# Kiwi_Rev_3_1S.net
KiCad netlist of a schematic drawn in EAGLE
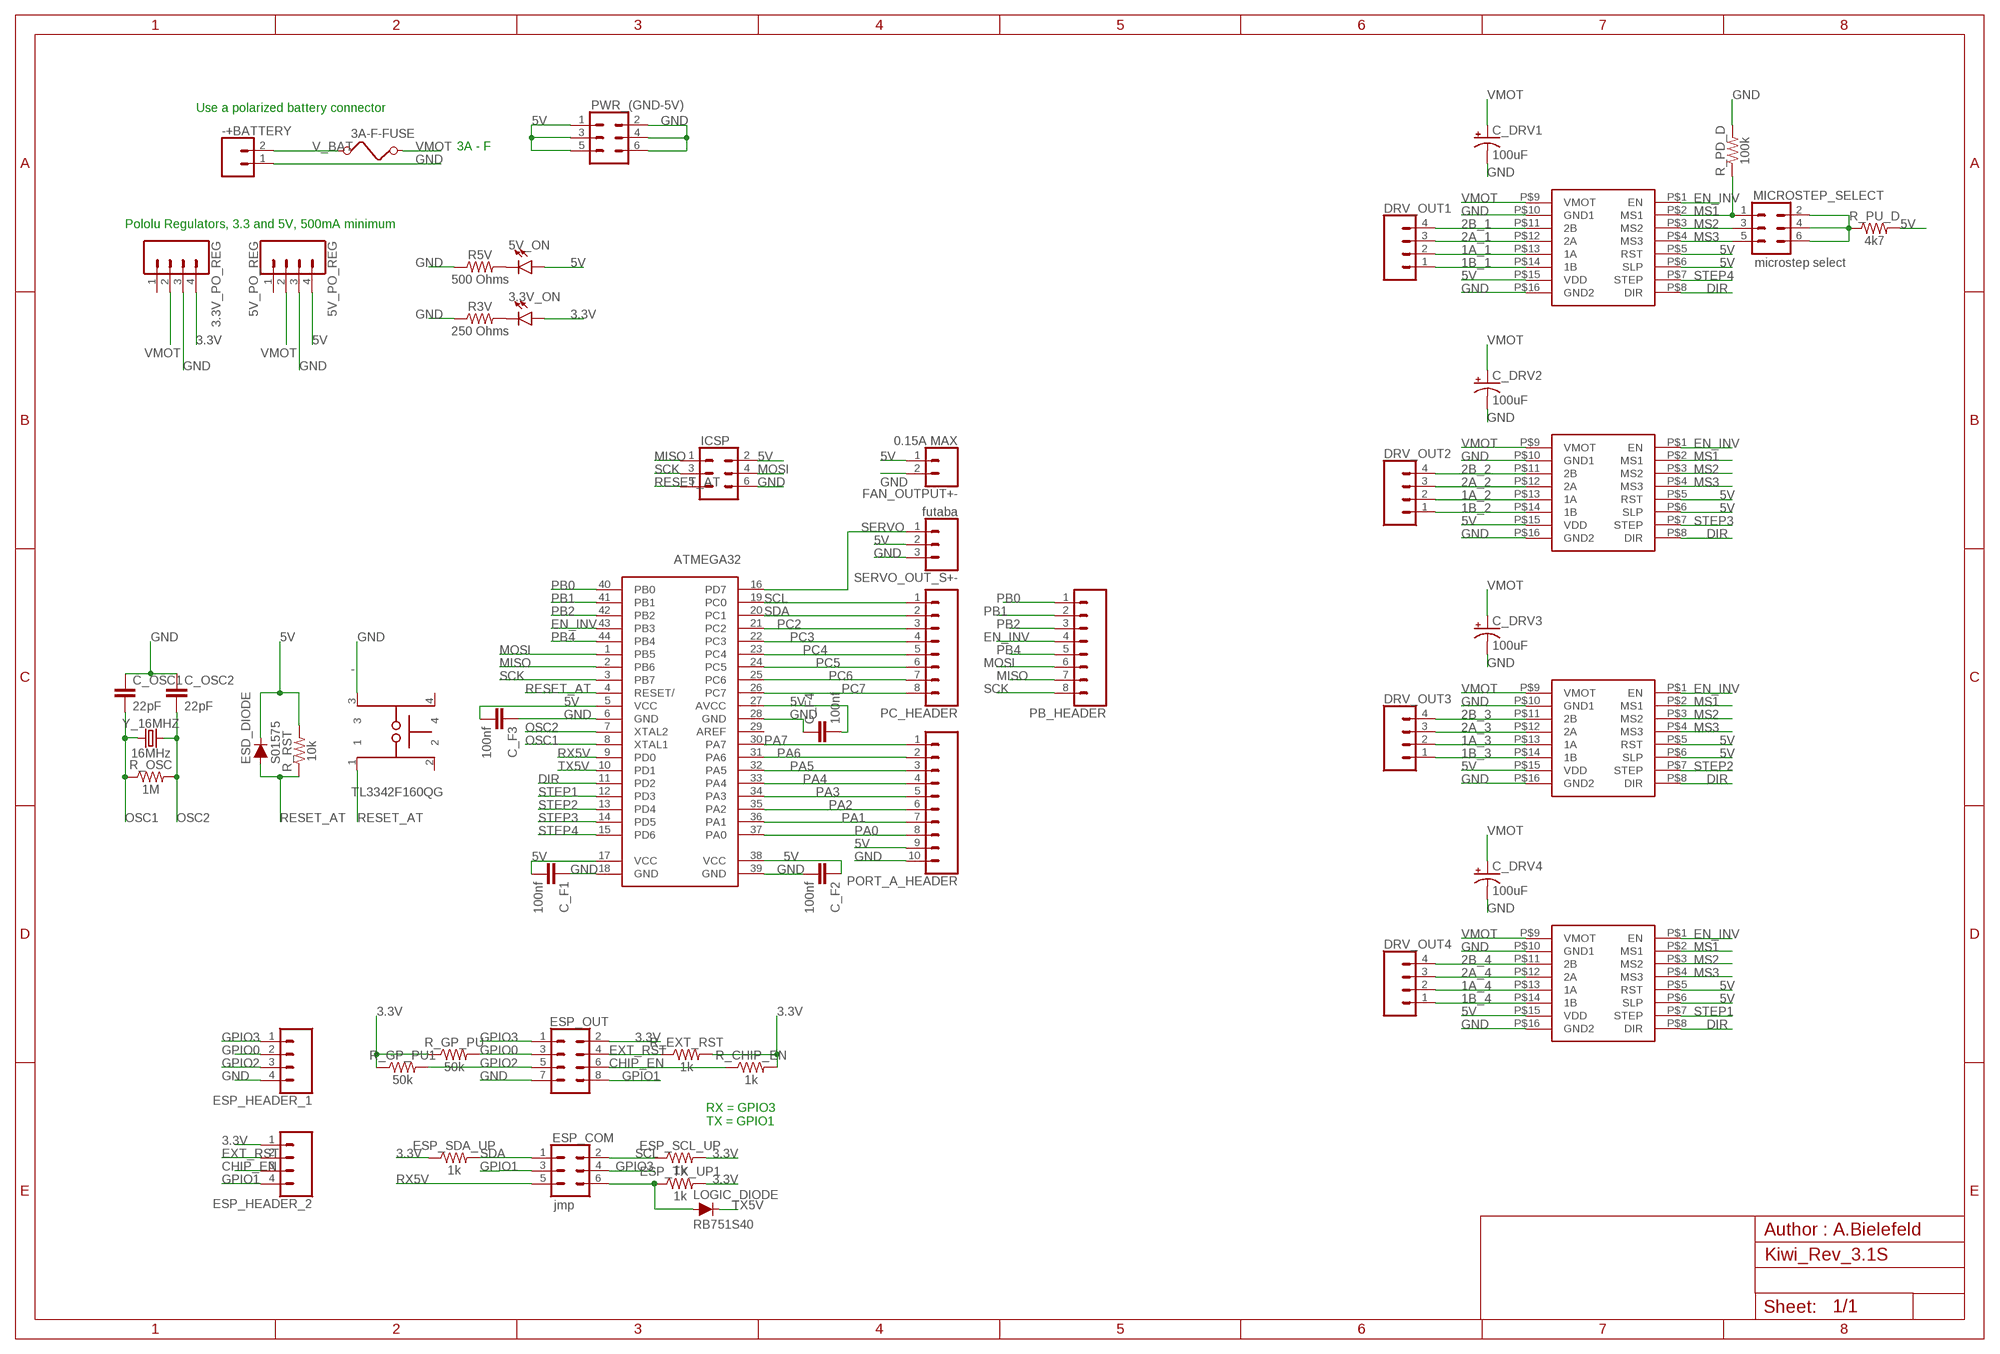
[diagram p0: schematic, sheet 1]

(export (version "E")
  (design (tool "Eeschema 10.0.6"))
  (components
    (comp (ref "-")
      (value "TL3342F160QG")
      (footprint "eagle-import:SW_TL3342F160QG")
      (fields (field (name "MF") "E-Switch"))
      (libsource (lib "eagle-import") (part "TL3342F160QG"))
    )
    (comp (ref "-+BATTERY")
      (value "CONN_023.5MM")
      (footprint "eagle-import:SCREWTERMINAL-3.5MM-2")
      (libsource (lib "eagle-import") (part "CONN_023.5MM"))
    )
    (comp (ref "3.3V_ON")
      (value "LED1206")
      (footprint "eagle-import:LED-1206")
      (libsource (lib "eagle-import") (part "LED1206"))
    )
    (comp (ref "3.3V_PO_REG")
      (value "CONN_04")
      (footprint "eagle-import:1X04")
      (libsource (lib "eagle-import") (part "CONN_04"))
    )
    (comp (ref "3A-F-FUSE")
      (value "FUSE")
      (footprint "eagle-import:FUSE")
      (libsource (lib "eagle-import") (part "FUSE"))
    )
    (comp (ref "5V_ON")
      (value "LED1206")
      (footprint "eagle-import:LED-1206")
      (libsource (lib "eagle-import") (part "LED1206"))
    )
    (comp (ref "5V_PO_REG")
      (value "5V_PO_REG")
      (footprint "eagle-import:1X04")
      (libsource (lib "eagle-import") (part "CONN_04"))
    )
    (comp (ref "ATMEGA32")
      (value "ATMEGA32")
      (footprint "eagle-import:QFP80P1200X1200X120-44N")
      (libsource (lib "eagle-import") (part "ATMEGA32"))
    )
    (comp (ref "C_DRV1")
      (value "100uF")
      (footprint "eagle-import:CPOL-RADIAL-2.5MM-6.5MM")
      (libsource (lib "eagle-import") (part "100UF-POLAR-RADIAL-2.5MM-25V-20%"))
    )
    (comp (ref "C_DRV2")
      (value "100uF")
      (footprint "eagle-import:CPOL-RADIAL-2.5MM-6.5MM")
      (libsource (lib "eagle-import") (part "100UF-POLAR-RADIAL-2.5MM-25V-20%"))
    )
    (comp (ref "C_DRV3")
      (value "100uF")
      (footprint "eagle-import:CPOL-RADIAL-2.5MM-6.5MM")
      (libsource (lib "eagle-import") (part "100UF-POLAR-RADIAL-2.5MM-25V-20%"))
    )
    (comp (ref "C_DRV4")
      (value "100uF")
      (footprint "eagle-import:CPOL-RADIAL-2.5MM-6.5MM")
      (libsource (lib "eagle-import") (part "100UF-POLAR-RADIAL-2.5MM-25V-20%"))
    )
    (comp (ref "C_F1")
      (value "100nf")
      (footprint "eagle-import:0603")
      (libsource (lib "eagle-import") (part "2.2UF-0603-10V-20%"))
    )
    (comp (ref "C_F2")
      (value "100nf")
      (footprint "eagle-import:0603")
      (libsource (lib "eagle-import") (part "2.2UF-0603-10V-20%"))
    )
    (comp (ref "C_F3")
      (value "100nf")
      (footprint "eagle-import:0603")
      (libsource (lib "eagle-import") (part "2.2UF-0603-10V-20%"))
    )
    (comp (ref "C_F4")
      (value "100nf")
      (footprint "eagle-import:0603")
      (libsource (lib "eagle-import") (part "2.2UF-0603-10V-20%"))
    )
    (comp (ref "C_OSC1")
      (value "22pF")
      (footprint "eagle-import:1206")
      (libsource (lib "eagle-import") (part "2.2UF-1206-50V-10%"))
    )
    (comp (ref "C_OSC2")
      (value "22pF")
      (footprint "eagle-import:1206")
      (libsource (lib "eagle-import") (part "2.2UF-1206-50V-10%"))
    )
    (comp (ref "DRIVER1")
      (value "POLOLU_A4988")
      (footprint "eagle-import:POLOLU_CARRIER")
      (libsource (lib "eagle-import") (part "POLOLU_A4988"))
    )
    (comp (ref "DRIVER2")
      (value "POLOLU_A4988")
      (footprint "eagle-import:POLOLU_CARRIER")
      (libsource (lib "eagle-import") (part "POLOLU_A4988"))
    )
    (comp (ref "DRIVER3")
      (value "POLOLU_A4988")
      (footprint "eagle-import:POLOLU_CARRIER")
      (libsource (lib "eagle-import") (part "POLOLU_A4988"))
    )
    (comp (ref "DRIVER4")
      (value "POLOLU_A4988")
      (footprint "eagle-import:POLOLU_CARRIER")
      (libsource (lib "eagle-import") (part "POLOLU_A4988"))
    )
    (comp (ref "DRV_OUT1")
      (value "CONN_04")
      (footprint "eagle-import:1X04")
      (libsource (lib "eagle-import") (part "CONN_04"))
    )
    (comp (ref "DRV_OUT2")
      (value "CONN_04")
      (footprint "eagle-import:1X04")
      (libsource (lib "eagle-import") (part "CONN_04"))
    )
    (comp (ref "DRV_OUT3")
      (value "CONN_04")
      (footprint "eagle-import:1X04")
      (libsource (lib "eagle-import") (part "CONN_04"))
    )
    (comp (ref "DRV_OUT4")
      (value "CONN_04")
      (footprint "eagle-import:1X04")
      (libsource (lib "eagle-import") (part "CONN_04"))
    )
    (comp (ref "ESD_DIODE")
      (value "S01575")
      (footprint "eagle-import:1206")
      (libsource (lib "eagle-import") (part "S01575"))
    )
    (comp (ref "ESP_COM")
      (value "jmp")
      (footprint "eagle-import:2X3")
      (libsource (lib "eagle-import") (part "CONN_03X2FEMALE"))
    )
    (comp (ref "ESP_HEADER_1")
      (value "CONN_04")
      (footprint "eagle-import:1X04")
      (libsource (lib "eagle-import") (part "CONN_04"))
    )
    (comp (ref "ESP_HEADER_2")
      (value "CONN_04")
      (footprint "eagle-import:1X04")
      (libsource (lib "eagle-import") (part "CONN_04"))
    )
    (comp (ref "ESP_OUT")
      (value "CONN_04X2")
      (footprint "eagle-import:2X4")
      (libsource (lib "eagle-import") (part "CONN_04X2"))
    )
    (comp (ref "ESP_SCL_UP")
      (value "1k")
      (footprint "eagle-import:1206")
      (libsource (lib "eagle-import") (part "10OHM-1206-1/4W-1%"))
    )
    (comp (ref "ESP_SDA_UP")
      (value "1k")
      (footprint "eagle-import:1206")
      (libsource (lib "eagle-import") (part "10OHM-1206-1/4W-1%"))
    )
    (comp (ref "ESP_TX_UP1")
      (value "1k")
      (footprint "eagle-import:1206")
      (libsource (lib "eagle-import") (part "10OHM-1206-1/4W-1%"))
    )
    (comp (ref "FAN_OUTPUT+-")
      (value "0.15A MAX")
      (footprint "eagle-import:1X02")
      (libsource (lib "eagle-import") (part "CONN_02"))
    )
    (comp (ref "ICSP")
      (value "CONN_03X22X3_SILK_MALE_PTH")
      (footprint "eagle-import:2X3")
      (libsource (lib "eagle-import") (part "CONN_03X22X3_SILK_MALE_PTH"))
    )
    (comp (ref "LOGIC_DIODE")
      (value "RB751S40")
      (footprint "eagle-import:SOD523")
      (libsource (lib "eagle-import") (part "RB751S40"))
    )
    (comp (ref "MICROSTEP_SELECT")
      (value "microstep select")
      (footprint "eagle-import:2X3")
      (libsource (lib "eagle-import") (part "CONN_03X2FEMALE"))
    )
    (comp (ref "PB_HEADER")
      (value "CONN_08\"")
      (footprint "eagle-import:1X08")
      (libsource (lib "eagle-import") (part "CONN_08{dblquote}"))
    )
    (comp (ref "PC_HEADER")
      (value "CONN_08\"")
      (footprint "eagle-import:1X08")
      (libsource (lib "eagle-import") (part "CONN_08{dblquote}"))
    )
    (comp (ref "PORT_A_HEADER")
      (value "CONN_10\"")
      (footprint "eagle-import:1X10")
      (libsource (lib "eagle-import") (part "CONN_10{dblquote}"))
    )
    (comp (ref "PWR_(GND-5V)")
      (value "CONN_03X22X3_SILK_MALE_PTH")
      (footprint "eagle-import:2X3")
      (libsource (lib "eagle-import") (part "CONN_03X22X3_SILK_MALE_PTH"))
    )
    (comp (ref "R3V")
      (value "250 Ohms")
      (footprint "eagle-import:1206")
      (libsource (lib "eagle-import") (part "10OHM-1206-1/4W-1%"))
    )
    (comp (ref "R5V")
      (value "500 Ohms")
      (footprint "eagle-import:1206")
      (libsource (lib "eagle-import") (part "10OHM-1206-1/4W-1%"))
    )
    (comp (ref "R_CHIP_EN")
      (value "1k")
      (footprint "eagle-import:1206")
      (libsource (lib "eagle-import") (part "10OHM-1206-1/4W-1%"))
    )
    (comp (ref "R_EXT_RST")
      (value "1k")
      (footprint "eagle-import:1206")
      (libsource (lib "eagle-import") (part "10OHM-1206-1/4W-1%"))
    )
    (comp (ref "R_GP_PU")
      (value "50k")
      (footprint "eagle-import:1206")
      (libsource (lib "eagle-import") (part "10OHM-1206-1/4W-1%"))
    )
    (comp (ref "R_GP_PU1")
      (value "50k")
      (footprint "eagle-import:1206")
      (libsource (lib "eagle-import") (part "10OHM-1206-1/4W-1%"))
    )
    (comp (ref "R_OSC")
      (value "1M")
      (footprint "eagle-import:1206")
      (libsource (lib "eagle-import") (part "10OHM-1206-1/4W-1%"))
    )
    (comp (ref "R_PD_D")
      (value "100k")
      (footprint "eagle-import:1206")
      (libsource (lib "eagle-import") (part "10OHM-1206-1/4W-1%"))
    )
    (comp (ref "R_PU_D")
      (value "4k7")
      (footprint "eagle-import:1206")
      (libsource (lib "eagle-import") (part "10OHM-1206-1/4W-1%"))
    )
    (comp (ref "R_RST")
      (value "10k")
      (footprint "eagle-import:1206")
      (libsource (lib "eagle-import") (part "10OHM-1206-1/4W-1%"))
    )
    (comp (ref "SERVO_OUT_S+-")
      (value "futaba")
      (footprint "eagle-import:1X03")
      (libsource (lib "eagle-import") (part "CONN_03"))
    )
    (comp (ref "Y_16MHZ")
      (value "16MHz")
      (footprint "eagle-import:HC49US")
      (libsource (lib "eagle-import") (part "CRYSTAL-16MHZPTH-HC49US"))
    )
  )
  (nets
    (net (code "1") (name "/1A_1") (class "Default")
      (node (ref "DRIVER1") (pin "P$13") (pinfunction "1A_P$13") (pintype "output"))
      (node (ref "DRV_OUT1") (pin "2") (pinfunction "2_2") (pintype "passive"))
    )
    (net (code "2") (name "/1A_2") (class "Default")
      (node (ref "DRIVER2") (pin "P$13") (pinfunction "1A_P$13") (pintype "output"))
      (node (ref "DRV_OUT2") (pin "2") (pinfunction "2_2") (pintype "passive"))
    )
    (net (code "3") (name "/1A_3") (class "Default")
      (node (ref "DRIVER3") (pin "P$13") (pinfunction "1A_P$13") (pintype "output"))
      (node (ref "DRV_OUT3") (pin "2") (pinfunction "2_2") (pintype "passive"))
    )
    (net (code "4") (name "/1A_4") (class "Default")
      (node (ref "DRIVER4") (pin "P$13") (pinfunction "1A_P$13") (pintype "output"))
      (node (ref "DRV_OUT4") (pin "2") (pinfunction "2_2") (pintype "passive"))
    )
    (net (code "5") (name "/1B_1") (class "Default")
      (node (ref "DRIVER1") (pin "P$14") (pinfunction "1B_P$14") (pintype "output"))
      (node (ref "DRV_OUT1") (pin "1") (pinfunction "1_1") (pintype "passive"))
    )
    (net (code "6") (name "/1B_2") (class "Default")
      (node (ref "DRIVER2") (pin "P$14") (pinfunction "1B_P$14") (pintype "output"))
      (node (ref "DRV_OUT2") (pin "1") (pinfunction "1_1") (pintype "passive"))
    )
    (net (code "7") (name "/1B_3") (class "Default")
      (node (ref "DRIVER3") (pin "P$14") (pinfunction "1B_P$14") (pintype "output"))
      (node (ref "DRV_OUT3") (pin "1") (pinfunction "1_1") (pintype "passive"))
    )
    (net (code "8") (name "/1B_4") (class "Default")
      (node (ref "DRIVER4") (pin "P$14") (pinfunction "1B_P$14") (pintype "output"))
      (node (ref "DRV_OUT4") (pin "1") (pinfunction "1_1") (pintype "passive"))
    )
    (net (code "9") (name "/2A_1") (class "Default")
      (node (ref "DRIVER1") (pin "P$12") (pinfunction "2A_P$12") (pintype "output"))
      (node (ref "DRV_OUT1") (pin "3") (pinfunction "3_3") (pintype "passive"))
    )
    (net (code "10") (name "/2A_2") (class "Default")
      (node (ref "DRIVER2") (pin "P$12") (pinfunction "2A_P$12") (pintype "output"))
      (node (ref "DRV_OUT2") (pin "3") (pinfunction "3_3") (pintype "passive"))
    )
    (net (code "11") (name "/2A_3") (class "Default")
      (node (ref "DRIVER3") (pin "P$12") (pinfunction "2A_P$12") (pintype "output"))
      (node (ref "DRV_OUT3") (pin "3") (pinfunction "3_3") (pintype "passive"))
    )
    (net (code "12") (name "/2A_4") (class "Default")
      (node (ref "DRIVER4") (pin "P$12") (pinfunction "2A_P$12") (pintype "output"))
      (node (ref "DRV_OUT4") (pin "3") (pinfunction "3_3") (pintype "passive"))
    )
    (net (code "13") (name "/2B_1") (class "Default")
      (node (ref "DRIVER1") (pin "P$11") (pinfunction "2B_P$11") (pintype "output"))
      (node (ref "DRV_OUT1") (pin "4") (pinfunction "4_4") (pintype "passive"))
    )
    (net (code "14") (name "/2B_2") (class "Default")
      (node (ref "DRIVER2") (pin "P$11") (pinfunction "2B_P$11") (pintype "output"))
      (node (ref "DRV_OUT2") (pin "4") (pinfunction "4_4") (pintype "passive"))
    )
    (net (code "15") (name "/2B_3") (class "Default")
      (node (ref "DRIVER3") (pin "P$11") (pinfunction "2B_P$11") (pintype "output"))
      (node (ref "DRV_OUT3") (pin "4") (pinfunction "4_4") (pintype "passive"))
    )
    (net (code "16") (name "/2B_4") (class "Default")
      (node (ref "DRIVER4") (pin "P$11") (pinfunction "2B_P$11") (pintype "output"))
      (node (ref "DRV_OUT4") (pin "4") (pinfunction "4_4") (pintype "passive"))
    )
    (net (code "17") (name "/3.3V") (class "Default")
      (node (ref "3.3V_ON") (pin "A") (pinfunction "A_A") (pintype "passive"))
      (node (ref "3.3V_PO_REG") (pin "4") (pinfunction "4_4") (pintype "passive"))
      (node (ref "ESP_HEADER_2") (pin "1") (pinfunction "1_1") (pintype "passive"))
      (node (ref "ESP_OUT") (pin "2") (pinfunction "2_2") (pintype "passive"))
      (node (ref "ESP_SCL_UP") (pin "2") (pinfunction "2_2") (pintype "passive"))
      (node (ref "ESP_SDA_UP") (pin "1") (pinfunction "1_1") (pintype "passive"))
      (node (ref "ESP_TX_UP1") (pin "2") (pinfunction "2_2") (pintype "passive"))
      (node (ref "R_CHIP_EN") (pin "2") (pinfunction "2_2") (pintype "passive"))
      (node (ref "R_EXT_RST") (pin "2") (pinfunction "2_2") (pintype "passive"))
      (node (ref "R_GP_PU") (pin "1") (pinfunction "1_1") (pintype "passive"))
      (node (ref "R_GP_PU1") (pin "1") (pinfunction "1_1") (pintype "passive"))
    )
    (net (code "18") (name "/5V") (class "Default")
      (node (ref "5V_ON") (pin "A") (pinfunction "A_A") (pintype "passive"))
      (node (ref "5V_PO_REG") (pin "4") (pinfunction "4_4") (pintype "passive"))
      (node (ref "ATMEGA32") (pin "17") (pinfunction "VCC_17") (pintype "bidirectional"))
      (node (ref "ATMEGA32") (pin "27") (pinfunction "AVCC_27") (pintype "bidirectional"))
      (node (ref "ATMEGA32") (pin "38") (pinfunction "VCC_38") (pintype "bidirectional"))
      (node (ref "ATMEGA32") (pin "5") (pinfunction "VCC_5") (pintype "bidirectional"))
      (node (ref "C_F1") (pin "2") (pinfunction "2_2") (pintype "passive"))
      (node (ref "C_F2") (pin "1") (pinfunction "1_1") (pintype "passive"))
      (node (ref "C_F3") (pin "2") (pinfunction "2_2") (pintype "passive"))
      (node (ref "C_F4") (pin "2") (pinfunction "2_2") (pintype "passive"))
      (node (ref "DRIVER1") (pin "P$15") (pinfunction "VDD_P$15") (pintype "power_in"))
      (node (ref "DRIVER1") (pin "P$5") (pinfunction "RST_P$5") (pintype "input"))
      (node (ref "DRIVER1") (pin "P$6") (pinfunction "SLP_P$6") (pintype "input"))
      (node (ref "DRIVER2") (pin "P$15") (pinfunction "VDD_P$15") (pintype "power_in"))
      (node (ref "DRIVER2") (pin "P$5") (pinfunction "RST_P$5") (pintype "input"))
      (node (ref "DRIVER2") (pin "P$6") (pinfunction "SLP_P$6") (pintype "input"))
      (node (ref "DRIVER3") (pin "P$15") (pinfunction "VDD_P$15") (pintype "power_in"))
      (node (ref "DRIVER3") (pin "P$5") (pinfunction "RST_P$5") (pintype "input"))
      (node (ref "DRIVER3") (pin "P$6") (pinfunction "SLP_P$6") (pintype "input"))
      (node (ref "DRIVER4") (pin "P$15") (pinfunction "VDD_P$15") (pintype "power_in"))
      (node (ref "DRIVER4") (pin "P$5") (pinfunction "RST_P$5") (pintype "input"))
      (node (ref "DRIVER4") (pin "P$6") (pinfunction "SLP_P$6") (pintype "input"))
      (node (ref "ESD_DIODE") (pin "2") (pinfunction "C_2") (pintype "passive"))
      (node (ref "FAN_OUTPUT+-") (pin "1") (pinfunction "1_1") (pintype "passive"))
      (node (ref "ICSP") (pin "2") (pinfunction "2_2") (pintype "bidirectional"))
      (node (ref "PORT_A_HEADER") (pin "9") (pinfunction "9_9") (pintype "passive"))
      (node (ref "PWR_(GND-5V)") (pin "1") (pinfunction "1_1") (pintype "bidirectional"))
      (node (ref "PWR_(GND-5V)") (pin "3") (pinfunction "3_3") (pintype "bidirectional"))
      (node (ref "PWR_(GND-5V)") (pin "5") (pinfunction "5_5") (pintype "bidirectional"))
      (node (ref "R_PU_D") (pin "2") (pinfunction "2_2") (pintype "passive"))
      (node (ref "R_RST") (pin "2") (pinfunction "2_2") (pintype "passive"))
      (node (ref "SERVO_OUT_S+-") (pin "2") (pinfunction "2_2") (pintype "passive"))
    )
    (net (code "19") (name "/CHIP_EN") (class "Default")
      (node (ref "ESP_HEADER_2") (pin "3") (pinfunction "3_3") (pintype "passive"))
      (node (ref "ESP_OUT") (pin "6") (pinfunction "6_6") (pintype "passive"))
      (node (ref "R_CHIP_EN") (pin "1") (pinfunction "1_1") (pintype "passive"))
    )
    (net (code "20") (name "/DIR") (class "Default")
      (node (ref "ATMEGA32") (pin "11") (pinfunction "PD2_11") (pintype "bidirectional"))
      (node (ref "DRIVER1") (pin "P$8") (pinfunction "DIR_P$8") (pintype "input"))
      (node (ref "DRIVER2") (pin "P$8") (pinfunction "DIR_P$8") (pintype "input"))
      (node (ref "DRIVER3") (pin "P$8") (pinfunction "DIR_P$8") (pintype "input"))
      (node (ref "DRIVER4") (pin "P$8") (pinfunction "DIR_P$8") (pintype "input"))
    )
    (net (code "21") (name "/EN_INV") (class "Default")
      (node (ref "ATMEGA32") (pin "43") (pinfunction "PB3_43") (pintype "bidirectional"))
      (node (ref "DRIVER1") (pin "P$1") (pinfunction "EN_P$1") (pintype "input"))
      (node (ref "DRIVER2") (pin "P$1") (pinfunction "EN_P$1") (pintype "input"))
      (node (ref "DRIVER3") (pin "P$1") (pinfunction "EN_P$1") (pintype "input"))
      (node (ref "DRIVER4") (pin "P$1") (pinfunction "EN_P$1") (pintype "input"))
      (node (ref "PB_HEADER") (pin "4") (pinfunction "4_4") (pintype "passive"))
    )
    (net (code "22") (name "/EXT_RST") (class "Default")
      (node (ref "ESP_HEADER_2") (pin "2") (pinfunction "2_2") (pintype "passive"))
      (node (ref "ESP_OUT") (pin "4") (pinfunction "4_4") (pintype "passive"))
      (node (ref "R_EXT_RST") (pin "1") (pinfunction "1_1") (pintype "passive"))
    )
    (net (code "23") (name "/GND") (class "Default")
      (node (ref "-") (pin "3") (pinfunction "3_3") (pintype "passive"))
      (node (ref "-+BATTERY") (pin "1") (pinfunction "1_1") (pintype "passive"))
      (node (ref "3.3V_PO_REG") (pin "3") (pinfunction "3_3") (pintype "passive"))
      (node (ref "5V_PO_REG") (pin "3") (pinfunction "3_3") (pintype "passive"))
      (node (ref "ATMEGA32") (pin "18") (pinfunction "GND_18") (pintype "bidirectional"))
      (node (ref "ATMEGA32") (pin "28") (pinfunction "GND_28") (pintype "bidirectional"))
      (node (ref "ATMEGA32") (pin "39") (pinfunction "GND_39") (pintype "bidirectional"))
      (node (ref "ATMEGA32") (pin "6") (pinfunction "GND_6") (pintype "bidirectional"))
      (node (ref "C_DRV1") (pin "2") (pinfunction "-_2") (pintype "passive"))
      (node (ref "C_DRV2") (pin "2") (pinfunction "-_2") (pintype "passive"))
      (node (ref "C_DRV3") (pin "2") (pinfunction "-_2") (pintype "passive"))
      (node (ref "C_DRV4") (pin "2") (pinfunction "-_2") (pintype "passive"))
      (node (ref "C_F1") (pin "1") (pinfunction "1_1") (pintype "passive"))
      (node (ref "C_F2") (pin "2") (pinfunction "2_2") (pintype "passive"))
      (node (ref "C_F3") (pin "1") (pinfunction "1_1") (pintype "passive"))
      (node (ref "C_F4") (pin "1") (pinfunction "1_1") (pintype "passive"))
      (node (ref "C_OSC1") (pin "1") (pinfunction "1_1") (pintype "passive"))
      (node (ref "C_OSC2") (pin "1") (pinfunction "1_1") (pintype "passive"))
      (node (ref "DRIVER1") (pin "P$10") (pinfunction "GND1_P$10") (pintype "power_in"))
      (node (ref "DRIVER1") (pin "P$16") (pinfunction "GND2_P$16") (pintype "power_in"))
      (node (ref "DRIVER2") (pin "P$10") (pinfunction "GND1_P$10") (pintype "power_in"))
      (node (ref "DRIVER2") (pin "P$16") (pinfunction "GND2_P$16") (pintype "power_in"))
      (node (ref "DRIVER3") (pin "P$10") (pinfunction "GND1_P$10") (pintype "power_in"))
      (node (ref "DRIVER3") (pin "P$16") (pinfunction "GND2_P$16") (pintype "power_in"))
      (node (ref "DRIVER4") (pin "P$10") (pinfunction "GND1_P$10") (pintype "power_in"))
      (node (ref "DRIVER4") (pin "P$16") (pinfunction "GND2_P$16") (pintype "power_in"))
      (node (ref "ESP_HEADER_1") (pin "4") (pinfunction "4_4") (pintype "passive"))
      (node (ref "ESP_OUT") (pin "7") (pinfunction "7_7") (pintype "passive"))
      (node (ref "FAN_OUTPUT+-") (pin "2") (pinfunction "2_2") (pintype "passive"))
      (node (ref "ICSP") (pin "6") (pinfunction "6_6") (pintype "bidirectional"))
      (node (ref "PORT_A_HEADER") (pin "10") (pinfunction "10_10") (pintype "passive"))
      (node (ref "PWR_(GND-5V)") (pin "2") (pinfunction "2_2") (pintype "bidirectional"))
      (node (ref "PWR_(GND-5V)") (pin "4") (pinfunction "4_4") (pintype "bidirectional"))
      (node (ref "PWR_(GND-5V)") (pin "6") (pinfunction "6_6") (pintype "bidirectional"))
      (node (ref "R3V") (pin "1") (pinfunction "1_1") (pintype "passive"))
      (node (ref "R5V") (pin "1") (pinfunction "1_1") (pintype "passive"))
      (node (ref "R_PD_D") (pin "2") (pinfunction "2_2") (pintype "passive"))
      (node (ref "SERVO_OUT_S+-") (pin "3") (pinfunction "3_3") (pintype "passive"))
    )
    (net (code "24") (name "/GPIO0") (class "Default")
      (node (ref "ESP_HEADER_1") (pin "2") (pinfunction "2_2") (pintype "passive"))
      (node (ref "ESP_OUT") (pin "3") (pinfunction "3_3") (pintype "passive"))
      (node (ref "R_GP_PU") (pin "2") (pinfunction "2_2") (pintype "passive"))
    )
    (net (code "25") (name "/GPIO1") (class "Default")
      (node (ref "ESP_COM") (pin "3") (pinfunction "3_3") (pintype "bidirectional"))
      (node (ref "ESP_HEADER_2") (pin "4") (pinfunction "4_4") (pintype "passive"))
      (node (ref "ESP_OUT") (pin "8") (pinfunction "8_8") (pintype "passive"))
    )
    (net (code "26") (name "/GPIO2") (class "Default")
      (node (ref "ESP_HEADER_1") (pin "3") (pinfunction "3_3") (pintype "passive"))
      (node (ref "ESP_OUT") (pin "5") (pinfunction "5_5") (pintype "passive"))
      (node (ref "R_GP_PU1") (pin "2") (pinfunction "2_2") (pintype "passive"))
    )
    (net (code "27") (name "/GPIO3") (class "Default")
      (node (ref "ESP_COM") (pin "4") (pinfunction "4_4") (pintype "bidirectional"))
      (node (ref "ESP_HEADER_1") (pin "1") (pinfunction "1_1") (pintype "passive"))
      (node (ref "ESP_OUT") (pin "1") (pinfunction "1_1") (pintype "passive"))
    )
    (net (code "28") (name "/MISO") (class "Default")
      (node (ref "ATMEGA32") (pin "2") (pinfunction "PB6_2") (pintype "bidirectional"))
      (node (ref "ICSP") (pin "1") (pinfunction "1_1") (pintype "bidirectional"))
      (node (ref "PB_HEADER") (pin "7") (pinfunction "7_7") (pintype "passive"))
    )
    (net (code "29") (name "/MOSI") (class "Default")
      (node (ref "ATMEGA32") (pin "1") (pinfunction "PB5_1") (pintype "bidirectional"))
      (node (ref "ICSP") (pin "4") (pinfunction "4_4") (pintype "bidirectional"))
      (node (ref "PB_HEADER") (pin "6") (pinfunction "6_6") (pintype "passive"))
    )
    (net (code "30") (name "/MS1") (class "Default")
      (node (ref "DRIVER1") (pin "P$2") (pinfunction "MS1_P$2") (pintype "input"))
      (node (ref "DRIVER2") (pin "P$2") (pinfunction "MS1_P$2") (pintype "input"))
      (node (ref "DRIVER3") (pin "P$2") (pinfunction "MS1_P$2") (pintype "input"))
      (node (ref "DRIVER4") (pin "P$2") (pinfunction "MS1_P$2") (pintype "input"))
      (node (ref "MICROSTEP_SELECT") (pin "1") (pinfunction "1_1") (pintype "bidirectional"))
      (node (ref "R_PD_D") (pin "1") (pinfunction "1_1") (pintype "passive"))
    )
    (net (code "31") (name "/MS2") (class "Default")
      (node (ref "DRIVER1") (pin "P$3") (pinfunction "MS2_P$3") (pintype "input"))
      (node (ref "DRIVER2") (pin "P$3") (pinfunction "MS2_P$3") (pintype "input"))
      (node (ref "DRIVER3") (pin "P$3") (pinfunction "MS2_P$3") (pintype "input"))
      (node (ref "DRIVER4") (pin "P$3") (pinfunction "MS2_P$3") (pintype "input"))
      (node (ref "MICROSTEP_SELECT") (pin "3") (pinfunction "3_3") (pintype "bidirectional"))
    )
    (net (code "32") (name "/MS3") (class "Default")
      (node (ref "DRIVER1") (pin "P$4") (pinfunction "MS3_P$4") (pintype "input"))
      (node (ref "DRIVER2") (pin "P$4") (pinfunction "MS3_P$4") (pintype "input"))
      (node (ref "DRIVER3") (pin "P$4") (pinfunction "MS3_P$4") (pintype "input"))
      (node (ref "DRIVER4") (pin "P$4") (pinfunction "MS3_P$4") (pintype "input"))
      (node (ref "MICROSTEP_SELECT") (pin "5") (pinfunction "5_5") (pintype "bidirectional"))
    )
    (net (code "33") (name "/OSC1") (class "Default")
      (node (ref "ATMEGA32") (pin "8") (pinfunction "XTAL1_8") (pintype "bidirectional"))
      (node (ref "C_OSC1") (pin "2") (pinfunction "2_2") (pintype "passive"))
      (node (ref "R_OSC") (pin "1") (pinfunction "1_1") (pintype "passive"))
      (node (ref "Y_16MHZ") (pin "1") (pinfunction "1_1") (pintype "passive"))
    )
    (net (code "34") (name "/OSC2") (class "Default")
      (node (ref "ATMEGA32") (pin "7") (pinfunction "XTAL2_7") (pintype "bidirectional"))
      (node (ref "C_OSC2") (pin "2") (pinfunction "2_2") (pintype "passive"))
      (node (ref "R_OSC") (pin "2") (pinfunction "2_2") (pintype "passive"))
      (node (ref "Y_16MHZ") (pin "2") (pinfunction "2_2") (pintype "passive"))
    )
    (net (code "35") (name "/PA0") (class "Default")
      (node (ref "ATMEGA32") (pin "37") (pinfunction "PA0_37") (pintype "bidirectional"))
      (node (ref "PORT_A_HEADER") (pin "8") (pinfunction "8_8") (pintype "passive"))
    )
    (net (code "36") (name "/PA1") (class "Default")
      (node (ref "ATMEGA32") (pin "36") (pinfunction "PA1_36") (pintype "bidirectional"))
      (node (ref "PORT_A_HEADER") (pin "7") (pinfunction "7_7") (pintype "passive"))
    )
    (net (code "37") (name "/PA2") (class "Default")
      (node (ref "ATMEGA32") (pin "35") (pinfunction "PA2_35") (pintype "bidirectional"))
      (node (ref "PORT_A_HEADER") (pin "6") (pinfunction "6_6") (pintype "passive"))
    )
    (net (code "38") (name "/PA3") (class "Default")
      (node (ref "ATMEGA32") (pin "34") (pinfunction "PA3_34") (pintype "bidirectional"))
      (node (ref "PORT_A_HEADER") (pin "5") (pinfunction "5_5") (pintype "passive"))
    )
    (net (code "39") (name "/PA4") (class "Default")
      (node (ref "ATMEGA32") (pin "33") (pinfunction "PA4_33") (pintype "bidirectional"))
      (node (ref "PORT_A_HEADER") (pin "4") (pinfunction "4_4") (pintype "passive"))
    )
    (net (code "40") (name "/PA5") (class "Default")
      (node (ref "ATMEGA32") (pin "32") (pinfunction "PA5_32") (pintype "bidirectional"))
      (node (ref "PORT_A_HEADER") (pin "3") (pinfunction "3_3") (pintype "passive"))
    )
    (net (code "41") (name "/PA6") (class "Default")
      (node (ref "ATMEGA32") (pin "31") (pinfunction "PA6_31") (pintype "bidirectional"))
      (node (ref "PORT_A_HEADER") (pin "2") (pinfunction "2_2") (pintype "passive"))
    )
    (net (code "42") (name "/PA7") (class "Default")
      (node (ref "ATMEGA32") (pin "30") (pinfunction "PA7_30") (pintype "bidirectional"))
      (node (ref "PORT_A_HEADER") (pin "1") (pinfunction "1_1") (pintype "passive"))
    )
    (net (code "43") (name "/PB0") (class "Default")
      (node (ref "ATMEGA32") (pin "40") (pinfunction "PB0_40") (pintype "bidirectional"))
      (node (ref "PB_HEADER") (pin "1") (pinfunction "1_1") (pintype "passive"))
    )
    (net (code "44") (name "/PB1") (class "Default")
      (node (ref "ATMEGA32") (pin "41") (pinfunction "PB1_41") (pintype "bidirectional"))
      (node (ref "PB_HEADER") (pin "2") (pinfunction "2_2") (pintype "passive"))
    )
    (net (code "45") (name "/PB2") (class "Default")
      (node (ref "ATMEGA32") (pin "42") (pinfunction "PB2_42") (pintype "bidirectional"))
      (node (ref "PB_HEADER") (pin "3") (pinfunction "3_3") (pintype "passive"))
    )
    (net (code "46") (name "/PB4") (class "Default")
      (node (ref "ATMEGA32") (pin "44") (pinfunction "PB4_44") (pintype "bidirectional"))
      (node (ref "PB_HEADER") (pin "5") (pinfunction "5_5") (pintype "passive"))
    )
    (net (code "47") (name "/PC2") (class "Default")
      (node (ref "ATMEGA32") (pin "21") (pinfunction "PC2_21") (pintype "bidirectional"))
      (node (ref "PC_HEADER") (pin "3") (pinfunction "3_3") (pintype "passive"))
    )
    (net (code "48") (name "/PC3") (class "Default")
      (node (ref "ATMEGA32") (pin "22") (pinfunction "PC3_22") (pintype "bidirectional"))
      (node (ref "PC_HEADER") (pin "4") (pinfunction "4_4") (pintype "passive"))
    )
    (net (code "49") (name "/PC4") (class "Default")
      (node (ref "ATMEGA32") (pin "23") (pinfunction "PC4_23") (pintype "bidirectional"))
      (node (ref "PC_HEADER") (pin "5") (pinfunction "5_5") (pintype "passive"))
    )
    (net (code "50") (name "/PC5") (class "Default")
      (node (ref "ATMEGA32") (pin "24") (pinfunction "PC5_24") (pintype "bidirectional"))
      (node (ref "PC_HEADER") (pin "6") (pinfunction "6_6") (pintype "passive"))
    )
    (net (code "51") (name "/PC6") (class "Default")
      (node (ref "ATMEGA32") (pin "25") (pinfunction "PC6_25") (pintype "bidirectional"))
      (node (ref "PC_HEADER") (pin "7") (pinfunction "7_7") (pintype "passive"))
    )
    (net (code "52") (name "/PC7") (class "Default")
      (node (ref "ATMEGA32") (pin "26") (pinfunction "PC7_26") (pintype "bidirectional"))
      (node (ref "PC_HEADER") (pin "8") (pinfunction "8_8") (pintype "passive"))
    )
    (net (code "53") (name "/RESET_AT") (class "Default")
      (node (ref "-") (pin "1") (pinfunction "1_1") (pintype "passive"))
      (node (ref "ATMEGA32") (pin "4") (pinfunction "RESET/_4") (pintype "bidirectional"))
      (node (ref "ESD_DIODE") (pin "1") (pinfunction "A_1") (pintype "passive"))
      (node (ref "ICSP") (pin "5") (pinfunction "5_5") (pintype "bidirectional"))
      (node (ref "R_RST") (pin "1") (pinfunction "1_1") (pintype "passive"))
    )
    (net (code "54") (name "/RX5V") (class "Default")
      (node (ref "ATMEGA32") (pin "9") (pinfunction "PD0_9") (pintype "bidirectional"))
      (node (ref "ESP_COM") (pin "5") (pinfunction "5_5") (pintype "bidirectional"))
    )
    (net (code "55") (name "/SCK") (class "Default")
      (node (ref "ATMEGA32") (pin "3") (pinfunction "PB7_3") (pintype "bidirectional"))
      (node (ref "ICSP") (pin "3") (pinfunction "3_3") (pintype "bidirectional"))
      (node (ref "PB_HEADER") (pin "8") (pinfunction "8_8") (pintype "passive"))
    )
    (net (code "56") (name "/SCL") (class "Default")
      (node (ref "ATMEGA32") (pin "19") (pinfunction "PC0_19") (pintype "bidirectional"))
      (node (ref "ESP_COM") (pin "2") (pinfunction "2_2") (pintype "bidirectional"))
      (node (ref "ESP_SCL_UP") (pin "1") (pinfunction "1_1") (pintype "passive"))
      (node (ref "PC_HEADER") (pin "1") (pinfunction "1_1") (pintype "passive"))
    )
    (net (code "57") (name "/SDA") (class "Default")
      (node (ref "ATMEGA32") (pin "20") (pinfunction "PC1_20") (pintype "bidirectional"))
      (node (ref "ESP_COM") (pin "1") (pinfunction "1_1") (pintype "bidirectional"))
      (node (ref "ESP_SDA_UP") (pin "2") (pinfunction "2_2") (pintype "passive"))
      (node (ref "PC_HEADER") (pin "2") (pinfunction "2_2") (pintype "passive"))
    )
    (net (code "58") (name "/SERVO") (class "Default")
      (node (ref "ATMEGA32") (pin "16") (pinfunction "PD7_16") (pintype "bidirectional"))
      (node (ref "SERVO_OUT_S+-") (pin "1") (pinfunction "1_1") (pintype "passive"))
    )
    (net (code "59") (name "/STEP1") (class "Default")
      (node (ref "ATMEGA32") (pin "12") (pinfunction "PD3_12") (pintype "bidirectional"))
      (node (ref "DRIVER4") (pin "P$7") (pinfunction "STEP_P$7") (pintype "input"))
    )
    (net (code "60") (name "/STEP2") (class "Default")
      (node (ref "ATMEGA32") (pin "13") (pinfunction "PD4_13") (pintype "bidirectional"))
      (node (ref "DRIVER3") (pin "P$7") (pinfunction "STEP_P$7") (pintype "input"))
    )
    (net (code "61") (name "/STEP3") (class "Default")
      (node (ref "ATMEGA32") (pin "14") (pinfunction "PD5_14") (pintype "bidirectional"))
      (node (ref "DRIVER2") (pin "P$7") (pinfunction "STEP_P$7") (pintype "input"))
    )
    (net (code "62") (name "/STEP4") (class "Default")
      (node (ref "ATMEGA32") (pin "15") (pinfunction "PD6_15") (pintype "bidirectional"))
      (node (ref "DRIVER1") (pin "P$7") (pinfunction "STEP_P$7") (pintype "input"))
    )
    (net (code "63") (name "/TX5V") (class "Default")
      (node (ref "ATMEGA32") (pin "10") (pinfunction "PD1_10") (pintype "bidirectional"))
      (node (ref "LOGIC_DIODE") (pin "C") (pinfunction "C_C") (pintype "passive"))
    )
    (net (code "64") (name "/VMOT") (class "Default")
      (node (ref "3.3V_PO_REG") (pin "2") (pinfunction "2_2") (pintype "passive"))
      (node (ref "3A-F-FUSE") (pin "2") (pinfunction "2_2") (pintype "passive"))
      (node (ref "5V_PO_REG") (pin "2") (pinfunction "2_2") (pintype "passive"))
      (node (ref "C_DRV1") (pin "1") (pinfunction "+_1") (pintype "passive"))
      (node (ref "C_DRV2") (pin "1") (pinfunction "+_1") (pintype "passive"))
      (node (ref "C_DRV3") (pin "1") (pinfunction "+_1") (pintype "passive"))
      (node (ref "C_DRV4") (pin "1") (pinfunction "+_1") (pintype "passive"))
      (node (ref "DRIVER1") (pin "P$9") (pinfunction "VMOT_P$9") (pintype "power_in"))
      (node (ref "DRIVER2") (pin "P$9") (pinfunction "VMOT_P$9") (pintype "power_in"))
      (node (ref "DRIVER3") (pin "P$9") (pinfunction "VMOT_P$9") (pintype "power_in"))
      (node (ref "DRIVER4") (pin "P$9") (pinfunction "VMOT_P$9") (pintype "power_in"))
    )
    (net (code "65") (name "/V_BAT") (class "Default")
      (node (ref "-+BATTERY") (pin "2") (pinfunction "2_2") (pintype "passive"))
      (node (ref "3A-F-FUSE") (pin "1") (pinfunction "1_1") (pintype "passive"))
    )
    (net (code "66") (name "Net-(3.3V_ON-PadC)") (class "Default")
      (node (ref "3.3V_ON") (pin "C") (pinfunction "C_C") (pintype "passive"))
      (node (ref "R3V") (pin "2") (pinfunction "2_2") (pintype "passive"))
    )
    (net (code "67") (name "Net-(5V_ON-PadC)") (class "Default")
      (node (ref "5V_ON") (pin "C") (pinfunction "C_C") (pintype "passive"))
      (node (ref "R5V") (pin "2") (pinfunction "2_2") (pintype "passive"))
    )
    (net (code "68") (name "Net-(ESP_COM-Pad6)") (class "Default")
      (node (ref "ESP_COM") (pin "6") (pinfunction "6_6") (pintype "bidirectional"))
      (node (ref "ESP_TX_UP1") (pin "1") (pinfunction "1_1") (pintype "passive"))
      (node (ref "LOGIC_DIODE") (pin "A") (pinfunction "A_A") (pintype "passive"))
    )
    (net (code "69") (name "Net-(MICROSTEP_SELECT-Pad2)") (class "Default")
      (node (ref "MICROSTEP_SELECT") (pin "2") (pinfunction "2_2") (pintype "bidirectional"))
      (node (ref "MICROSTEP_SELECT") (pin "4") (pinfunction "4_4") (pintype "bidirectional"))
      (node (ref "MICROSTEP_SELECT") (pin "6") (pinfunction "6_6") (pintype "bidirectional"))
      (node (ref "R_PU_D") (pin "1") (pinfunction "1_1") (pintype "passive"))
    )
    (net (code "70") (name "unconnected-(--Pad2)") (class "Default")
      (node (ref "-") (pin "2") (pinfunction "2_2") (pintype "passive"))
    )
    (net (code "71") (name "unconnected-(--Pad4)") (class "Default")
      (node (ref "-") (pin "4") (pinfunction "4_4") (pintype "passive"))
    )
    (net (code "72") (name "unconnected-(3.3V_PO_REG-Pad1)") (class "Default")
      (node (ref "3.3V_PO_REG") (pin "1") (pinfunction "1_1") (pintype "passive"))
    )
    (net (code "73") (name "unconnected-(5V_PO_REG-Pad1)") (class "Default")
      (node (ref "5V_PO_REG") (pin "1") (pinfunction "1_1") (pintype "passive"))
    )
    (net (code "74") (name "unconnected-(ATMEGA32-AREF-Pad29)") (class "Default")
      (node (ref "ATMEGA32") (pin "29") (pinfunction "AREF_29") (pintype "bidirectional"))
    )
  )
)
